# PCB_sch_iter2.net
KiCad netlist of a schematic drawn in EAGLE
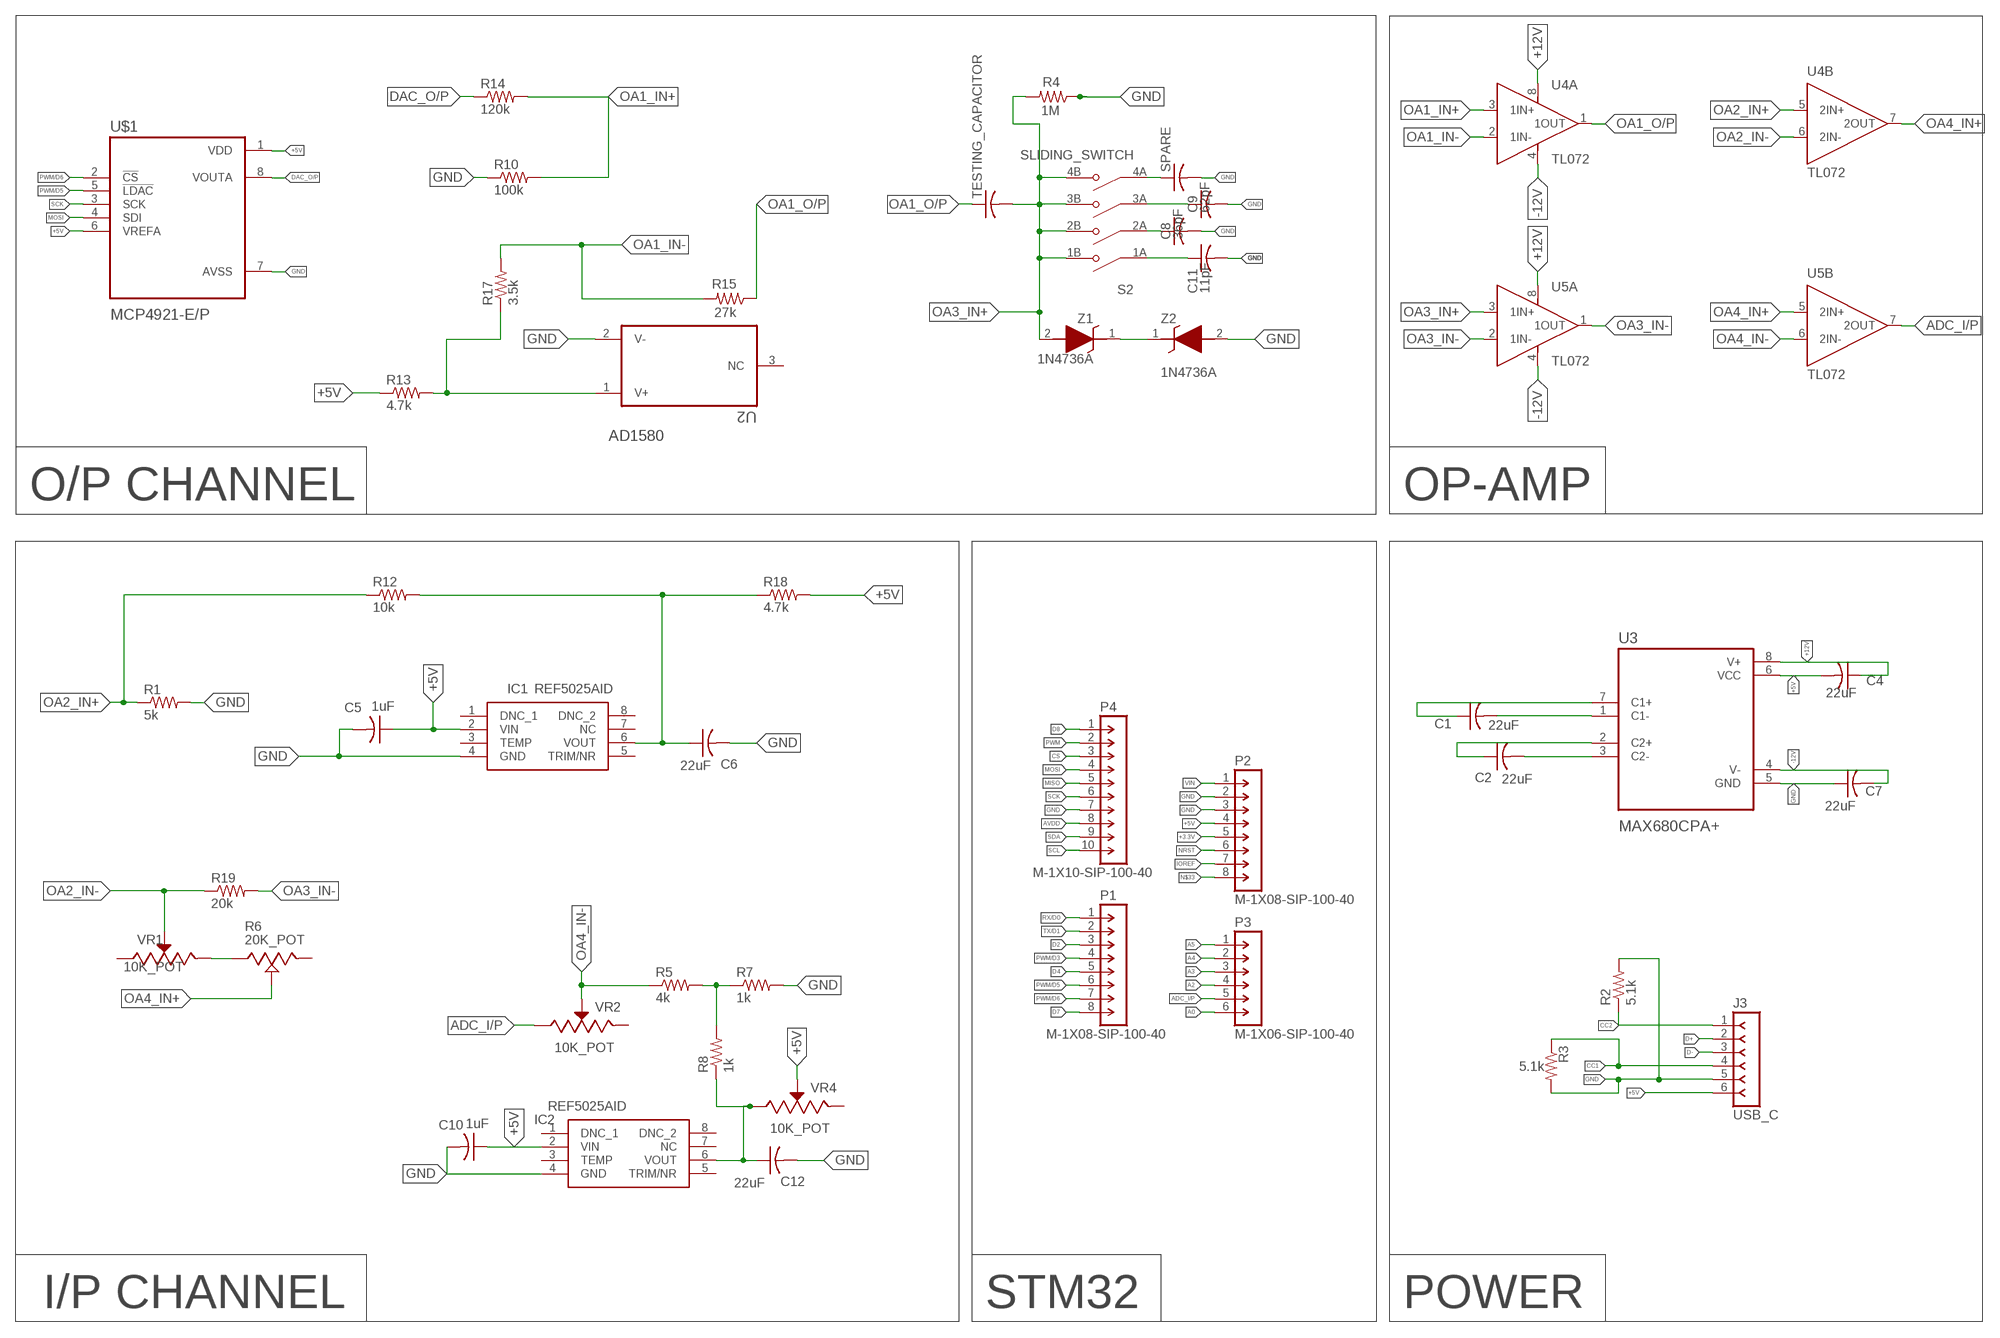
[diagram p0: schematic, sheet 1]

(export (version "E")
  (design (tool "Eeschema 10.0.6"))
  (components
    (comp (ref "C1")
      (value "22uF")
      (footprint "eagle-import:C1206")
      (libsource (lib "eagle-import") (part "C-USC1206"))
    )
    (comp (ref "C2")
      (value "22uF")
      (footprint "eagle-import:C1206")
      (libsource (lib "eagle-import") (part "C-USC1206"))
    )
    (comp (ref "C4")
      (value "22uF")
      (footprint "eagle-import:C1206")
      (libsource (lib "eagle-import") (part "C-USC1206"))
    )
    (comp (ref "C5")
      (value "1uF")
      (footprint "eagle-import:C1206")
      (libsource (lib "eagle-import") (part "C-USC1206"))
    )
    (comp (ref "C6")
      (value "22uF")
      (footprint "eagle-import:C1206")
      (libsource (lib "eagle-import") (part "C-USC1206"))
    )
    (comp (ref "C7")
      (value "22uF")
      (footprint "eagle-import:C1206")
      (libsource (lib "eagle-import") (part "C-USC1206"))
    )
    (comp (ref "C8")
      (value "36pF")
      (footprint "eagle-import:C0805")
      (libsource (lib "eagle-import") (part "C-USC0805"))
    )
    (comp (ref "C9")
      (value "62pF")
      (footprint "eagle-import:C0805")
      (libsource (lib "eagle-import") (part "C-USC0805"))
    )
    (comp (ref "C10")
      (value "1uF")
      (footprint "eagle-import:C1206")
      (libsource (lib "eagle-import") (part "C-USC1206"))
    )
    (comp (ref "C11")
      (value "11pF")
      (footprint "eagle-import:C0805")
      (fields (field (name "SPICEPREFIX") "C"))
      (libsource (lib "eagle-import") (part "C-USC0805"))
    )
    (comp (ref "C12")
      (value "22uF")
      (footprint "eagle-import:C1206")
      (libsource (lib "eagle-import") (part "C-USC1206"))
    )
    (comp (ref "IC1")
      (value "REF5025AID")
      (footprint "eagle-import:SOIC127P600X175-8N")
      (fields (field (name "MOUSER_PART_NUMBER") "595-REF5025AID"))
      (libsource (lib "eagle-import") (part "REF5025AID"))
    )
    (comp (ref "IC2")
      (value "REF5025AID")
      (footprint "eagle-import:SOIC127P600X175-8N")
      (fields (field (name "MOUSER_PART_NUMBER") "595-REF5025AID"))
      (libsource (lib "eagle-import") (part "REF5025AID"))
    )
    (comp (ref "J3")
      (value "USB_C")
      (footprint "eagle-import:SIP-100-06-40Y")
      (libsource (lib "eagle-import") (part "F-1X06-SIP-100-40Y"))
    )
    (comp (ref "P1")
      (value "M-1X08-SIP-100-40")
      (footprint "eagle-import:SIP-100-08-40")
      (libsource (lib "eagle-import") (part "M-1X08-SIP-100-40"))
    )
    (comp (ref "P2")
      (value "M-1X08-SIP-100-40")
      (footprint "eagle-import:SIP-100-08-40")
      (libsource (lib "eagle-import") (part "M-1X08-SIP-100-40"))
    )
    (comp (ref "P3")
      (value "M-1X06-SIP-100-40")
      (footprint "eagle-import:SIP-100-06-40")
      (libsource (lib "eagle-import") (part "M-1X06-SIP-100-40"))
    )
    (comp (ref "P4")
      (value "M-1X10-SIP-100-40")
      (footprint "eagle-import:SIP-100-10-40")
      (libsource (lib "eagle-import") (part "M-1X10-SIP-100-40"))
    )
    (comp (ref "R1")
      (value "5k")
      (footprint "eagle-import:M1206")
      (libsource (lib "eagle-import") (part "R-US_M1206"))
    )
    (comp (ref "R2")
      (value "5.1k")
      (footprint "eagle-import:R1206")
      (libsource (lib "eagle-import") (part "R-US_R1206"))
    )
    (comp (ref "R3")
      (value "5.1k")
      (footprint "eagle-import:R1206")
      (libsource (lib "eagle-import") (part "R-US_R1206"))
    )
    (comp (ref "R4")
      (value "1M")
      (footprint "eagle-import:M1206")
      (libsource (lib "eagle-import") (part "R-US_M1206"))
    )
    (comp (ref "R5")
      (value "4k")
      (footprint "eagle-import:M1206")
      (libsource (lib "eagle-import") (part "R-US_M1206"))
    )
    (comp (ref "R6")
      (value "20K_POT")
      (footprint "eagle-import:TRIM_3296X-1-203LF")
      (fields (field (name "MF") "Bourns") (field (name "MP") "3296X-1-203LF"))
      (libsource (lib "eagle-import") (part "3296X-1-203LF"))
    )
    (comp (ref "R7")
      (value "1k")
      (footprint "eagle-import:M1206")
      (libsource (lib "eagle-import") (part "R-US_M1206"))
    )
    (comp (ref "R8")
      (value "1k")
      (footprint "eagle-import:M1206")
      (libsource (lib "eagle-import") (part "R-US_M1206"))
    )
    (comp (ref "R10")
      (value "100k")
      (footprint "eagle-import:M1206")
      (libsource (lib "eagle-import") (part "R-US_M1206"))
    )
    (comp (ref "R12")
      (value "10k")
      (footprint "eagle-import:M1206")
      (libsource (lib "eagle-import") (part "R-US_M1206"))
    )
    (comp (ref "R13")
      (value "4.7k")
      (footprint "eagle-import:M1206")
      (libsource (lib "eagle-import") (part "R-US_M1206"))
    )
    (comp (ref "R14")
      (value "120k")
      (footprint "eagle-import:M1206")
      (libsource (lib "eagle-import") (part "R-US_M1206"))
    )
    (comp (ref "R15")
      (value "27k")
      (footprint "eagle-import:M1206")
      (libsource (lib "eagle-import") (part "R-US_M1206"))
    )
    (comp (ref "R17")
      (value "3.5k")
      (footprint "eagle-import:M1206")
      (libsource (lib "eagle-import") (part "R-US_M1206"))
    )
    (comp (ref "R18")
      (value "4.7k")
      (footprint "eagle-import:M1206")
      (libsource (lib "eagle-import") (part "R-US_M1206"))
    )
    (comp (ref "R19")
      (value "20k")
      (footprint "eagle-import:M1206")
      (libsource (lib "eagle-import") (part "R-US_M1206"))
    )
    (comp (ref "S2")
      (value "SLIDING_SWITCH")
      (footprint "eagle-import:SW_DS01C-254-S-04BE")
      (fields (field (name "MANUFACTURER") "CUI"))
      (libsource (lib "eagle-import") (part "DS01C-254-S-04BE"))
    )
    (comp (ref "SPARE")
      (value "C-USC0805")
      (footprint "eagle-import:C0805")
      (libsource (lib "eagle-import") (part "C-USC0805"))
    )
    (comp (ref "TESTING_CAPACITOR")
      (value "C-US050-030X075")
      (footprint "eagle-import:C050-030X075")
      (libsource (lib "eagle-import") (part "C-US050-030X075"))
    )
    (comp (ref "U$1")
      (value "MCP4921-E/P")
      (footprint "eagle-import:DIP787W46P254L927H533Q8")
      (fields (field (name "MF") "Microchip"))
      (libsource (lib "eagle-import") (part "MCP4921-E/P"))
    )
    (comp (ref "U2")
      (value "AD1580")
      (footprint "eagle-import:SOT96P237X112-3N")
      (libsource (lib "eagle-import") (part "AD1580BRTZ-R2-REEL7"))
    )
    (comp (ref "U3")
      (value "MAX680CPA+")
      (footprint "eagle-import:DIP794W47P254L991H457Q8")
      (fields (field (name "MF") "Maxim Integrated Products"))
      (libsource (lib "eagle-import") (part "MAX680CPA+"))
    )
    (comp (ref "U4")
      (value "TL072")
      (footprint "eagle-import:DIP794W45P254L1060H508Q8")
      (fields (field (name "MF") "Texas Instruments"))
      (libsource (lib "eagle-import") (part "TL072"))
    )
    (comp (ref "U5")
      (value "TL072")
      (footprint "eagle-import:DIP794W45P254L1060H508Q8")
      (fields (field (name "MF") "Texas Instruments"))
      (libsource (lib "eagle-import") (part "TL072"))
    )
    (comp (ref "VR1")
      (value "10K_POT")
      (footprint "eagle-import:TRIM_3296W-1-103RLF")
      (fields (field (name "MF") "Bourns") (field (name "MP") "3296W-1-103RLF"))
      (libsource (lib "eagle-import") (part "3296W-1-103RLF"))
    )
    (comp (ref "VR2")
      (value "10K_POT")
      (footprint "eagle-import:TRIM_3296W-1-103RLF")
      (fields (field (name "MF") "Bourns") (field (name "MP") "3296W-1-103RLF"))
      (libsource (lib "eagle-import") (part "3296W-1-103RLF"))
    )
    (comp (ref "VR4")
      (value "10K_POT")
      (footprint "eagle-import:TRIM_3296W-1-103RLF")
      (fields (field (name "MF") "Bourns") (field (name "MP") "3296W-1-103RLF"))
      (libsource (lib "eagle-import") (part "3296W-1-103RLF"))
    )
    (comp (ref "Z1")
      (value "1N4736A")
      (footprint "eagle-import:DIOAD1413W86L463D238")
      (fields (field (name "MOUSER_PART_NUMBER") "512-1N4736A"))
      (libsource (lib "eagle-import") (part "1N4736A"))
    )
    (comp (ref "Z2")
      (value "1N4736A")
      (footprint "eagle-import:DIOAD1413W86L463D238")
      (fields (field (name "MOUSER_PART_NUMBER") "512-1N4736A"))
      (libsource (lib "eagle-import") (part "1N4736A"))
    )
  )
  (nets
    (net (code "1") (name "+3.3V") (class "Default")
      (node (ref "P2") (pin "5") (pinfunction "5_5") (pintype "passive"))
    )
    (net (code "2") (name "+5V") (class "Default")
      (node (ref "C10") (pin "1") (pinfunction "1_1") (pintype "passive"))
      (node (ref "C4") (pin "2") (pinfunction "2_2") (pintype "passive"))
      (node (ref "C5") (pin "1") (pinfunction "1_1") (pintype "passive"))
      (node (ref "IC1") (pin "2") (pinfunction "VIN_2") (pintype "bidirectional"))
      (node (ref "IC2") (pin "2") (pinfunction "VIN_2") (pintype "bidirectional"))
      (node (ref "J3") (pin "6") (pinfunction "6_6") (pintype "passive"))
      (node (ref "P2") (pin "4") (pinfunction "4_4") (pintype "passive"))
      (node (ref "R13") (pin "1") (pinfunction "1_1") (pintype "passive"))
      (node (ref "R18") (pin "2") (pinfunction "2_2") (pintype "passive"))
      (node (ref "U$1") (pin "1") (pinfunction "VDD_1") (pintype "power_in"))
      (node (ref "U$1") (pin "6") (pinfunction "VREFA_6") (pintype "input"))
      (node (ref "U3") (pin "6") (pinfunction "VCC_6") (pintype "power_in"))
      (node (ref "VR4") (pin "2") (pinfunction "WIPER_2") (pintype "passive"))
    )
    (net (code "3") (name "+12V") (class "Default")
      (node (ref "C4") (pin "1") (pinfunction "1_1") (pintype "passive"))
      (node (ref "U3") (pin "8") (pinfunction "V+_8") (pintype "power_in"))
      (node (ref "U4") (pin "8") (pinfunction "VCC+_8") (pintype "power_in"))
      (node (ref "U5") (pin "8") (pinfunction "VCC+_8") (pintype "power_in"))
    )
    (net (code "4") (name "-12V") (class "Default")
      (node (ref "C7") (pin "2") (pinfunction "2_2") (pintype "passive"))
      (node (ref "U3") (pin "4") (pinfunction "V-_4") (pintype "power_in"))
      (node (ref "U4") (pin "4") (pinfunction "VCC-_4") (pintype "power_in"))
      (node (ref "U5") (pin "4") (pinfunction "VCC-_4") (pintype "power_in"))
    )
    (net (code "5") (name "A0") (class "Default")
      (node (ref "P3") (pin "6") (pinfunction "6_6") (pintype "passive"))
    )
    (net (code "6") (name "A2") (class "Default")
      (node (ref "P3") (pin "4") (pinfunction "4_4") (pintype "passive"))
    )
    (net (code "7") (name "A3") (class "Default")
      (node (ref "P3") (pin "3") (pinfunction "3_3") (pintype "passive"))
    )
    (net (code "8") (name "A4") (class "Default")
      (node (ref "P3") (pin "2") (pinfunction "2_2") (pintype "passive"))
    )
    (net (code "9") (name "A5") (class "Default")
      (node (ref "P3") (pin "1") (pinfunction "1_1") (pintype "passive"))
    )
    (net (code "10") (name "ADC_I{slash}P") (class "Default")
      (node (ref "P3") (pin "5") (pinfunction "5_5") (pintype "passive"))
      (node (ref "U5") (pin "7") (pinfunction "2OUT_7") (pintype "output"))
      (node (ref "VR2") (pin "1") (pinfunction "CCW_1") (pintype "passive"))
    )
    (net (code "11") (name "AVDD") (class "Default")
      (node (ref "P4") (pin "8") (pinfunction "8_8") (pintype "passive"))
    )
    (net (code "12") (name "CC1") (class "Default")
      (node (ref "J3") (pin "4") (pinfunction "4_4") (pintype "passive"))
      (node (ref "R3") (pin "1") (pinfunction "1_1") (pintype "passive"))
    )
    (net (code "13") (name "CC2") (class "Default")
      (node (ref "J3") (pin "1") (pinfunction "1_1") (pintype "passive"))
      (node (ref "R2") (pin "1") (pinfunction "1_1") (pintype "passive"))
    )
    (net (code "14") (name "CS") (class "Default")
      (node (ref "P4") (pin "3") (pinfunction "3_3") (pintype "passive"))
    )
    (net (code "15") (name "D+") (class "Default")
      (node (ref "J3") (pin "2") (pinfunction "2_2") (pintype "passive"))
    )
    (net (code "16") (name "D-") (class "Default")
      (node (ref "J3") (pin "3") (pinfunction "3_3") (pintype "passive"))
    )
    (net (code "17") (name "D2") (class "Default")
      (node (ref "P1") (pin "3") (pinfunction "3_3") (pintype "passive"))
    )
    (net (code "18") (name "D4") (class "Default")
      (node (ref "P1") (pin "5") (pinfunction "5_5") (pintype "passive"))
    )
    (net (code "19") (name "D7") (class "Default")
      (node (ref "P1") (pin "8") (pinfunction "8_8") (pintype "passive"))
    )
    (net (code "20") (name "D8") (class "Default")
      (node (ref "P4") (pin "1") (pinfunction "1_1") (pintype "passive"))
    )
    (net (code "21") (name "DAC_O{slash}P") (class "Default")
      (node (ref "R14") (pin "1") (pinfunction "1_1") (pintype "passive"))
      (node (ref "U$1") (pin "8") (pinfunction "VOUTA_8") (pintype "output"))
    )
    (net (code "22") (name "GND") (class "Default")
      (node (ref "C10") (pin "2") (pinfunction "2_2") (pintype "passive"))
      (node (ref "C11") (pin "2") (pinfunction "2_2") (pintype "passive"))
      (node (ref "C12") (pin "2") (pinfunction "2_2") (pintype "passive"))
      (node (ref "C5") (pin "2") (pinfunction "2_2") (pintype "passive"))
      (node (ref "C6") (pin "2") (pinfunction "2_2") (pintype "passive"))
      (node (ref "C7") (pin "1") (pinfunction "1_1") (pintype "passive"))
      (node (ref "C8") (pin "2") (pinfunction "2_2") (pintype "passive"))
      (node (ref "C9") (pin "2") (pinfunction "2_2") (pintype "passive"))
      (node (ref "IC1") (pin "4") (pinfunction "GND_4") (pintype "bidirectional"))
      (node (ref "IC2") (pin "4") (pinfunction "GND_4") (pintype "bidirectional"))
      (node (ref "J3") (pin "5") (pinfunction "5_5") (pintype "passive"))
      (node (ref "P2") (pin "2") (pinfunction "2_2") (pintype "passive"))
      (node (ref "P2") (pin "3") (pinfunction "3_3") (pintype "passive"))
      (node (ref "P4") (pin "7") (pinfunction "7_7") (pintype "passive"))
      (node (ref "R1") (pin "2") (pinfunction "2_2") (pintype "passive"))
      (node (ref "R10") (pin "1") (pinfunction "1_1") (pintype "passive"))
      (node (ref "R2") (pin "2") (pinfunction "2_2") (pintype "passive"))
      (node (ref "R3") (pin "2") (pinfunction "2_2") (pintype "passive"))
      (node (ref "R4") (pin "1") (pinfunction "1_1") (pintype "passive"))
      (node (ref "R7") (pin "2") (pinfunction "2_2") (pintype "passive"))
      (node (ref "SPARE") (pin "2") (pinfunction "2_2") (pintype "passive"))
      (node (ref "U$1") (pin "7") (pinfunction "AVSS_7") (pintype "power_in"))
      (node (ref "U2") (pin "2") (pinfunction "V-_2") (pintype "power_in"))
      (node (ref "U3") (pin "5") (pinfunction "GND_5") (pintype "power_in"))
      (node (ref "Z2") (pin "2") (pinfunction "A_2") (pintype "bidirectional"))
    )
    (net (code "23") (name "IOREF") (class "Default")
      (node (ref "P2") (pin "7") (pinfunction "7_7") (pintype "passive"))
    )
    (net (code "24") (name "MISO") (class "Default")
      (node (ref "P4") (pin "5") (pinfunction "5_5") (pintype "passive"))
    )
    (net (code "25") (name "MOSI") (class "Default")
      (node (ref "P4") (pin "4") (pinfunction "4_4") (pintype "passive"))
      (node (ref "U$1") (pin "4") (pinfunction "SDI_4") (pintype "input"))
    )
    (net (code "26") (name "N$33") (class "Default")
      (node (ref "P2") (pin "8") (pinfunction "8_8") (pintype "passive"))
    )
    (net (code "27") (name "NRST") (class "Default")
      (node (ref "P2") (pin "6") (pinfunction "6_6") (pintype "passive"))
    )
    (net (code "28") (name "Net-(IC1-VOUT)") (class "Default")
      (node (ref "C6") (pin "1") (pinfunction "1_1") (pintype "passive"))
      (node (ref "IC1") (pin "6") (pinfunction "VOUT_6") (pintype "bidirectional"))
      (node (ref "R12") (pin "2") (pinfunction "2_2") (pintype "passive"))
      (node (ref "R18") (pin "1") (pinfunction "1_1") (pintype "passive"))
    )
    (net (code "29") (name "Net-(IC2-VOUT)") (class "Default")
      (node (ref "C12") (pin "1") (pinfunction "1_1") (pintype "passive"))
      (node (ref "IC2") (pin "6") (pinfunction "VOUT_6") (pintype "bidirectional"))
      (node (ref "R8") (pin "1") (pinfunction "1_1") (pintype "passive"))
      (node (ref "VR4") (pin "1") (pinfunction "CCW_1") (pintype "passive"))
    )
    (net (code "30") (name "Net-(R5-Pad2)") (class "Default")
      (node (ref "R5") (pin "2") (pinfunction "2_2") (pintype "passive"))
      (node (ref "R7") (pin "1") (pinfunction "1_1") (pintype "passive"))
      (node (ref "R8") (pin "2") (pinfunction "2_2") (pintype "passive"))
    )
    (net (code "31") (name "Net-(R6-CCW)") (class "Default")
      (node (ref "R6") (pin "1") (pinfunction "CCW_1") (pintype "passive"))
      (node (ref "VR1") (pin "3") (pinfunction "CW_3") (pintype "passive"))
    )
    (net (code "32") (name "Net-(S2-COM1)") (class "Default")
      (node (ref "C11") (pin "1") (pinfunction "1_1") (pintype "passive"))
      (node (ref "S2") (pin "1A") (pinfunction "COM1_1A") (pintype "passive"))
    )
    (net (code "33") (name "Net-(S2-COM2)") (class "Default")
      (node (ref "C8") (pin "1") (pinfunction "1_1") (pintype "passive"))
      (node (ref "S2") (pin "2A") (pinfunction "COM2_2A") (pintype "passive"))
    )
    (net (code "34") (name "Net-(S2-COM3)") (class "Default")
      (node (ref "C9") (pin "1") (pinfunction "1_1") (pintype "passive"))
      (node (ref "S2") (pin "3A") (pinfunction "COM3_3A") (pintype "passive"))
    )
    (net (code "35") (name "Net-(S2-COM4)") (class "Default")
      (node (ref "S2") (pin "4A") (pinfunction "COM4_4A") (pintype "passive"))
      (node (ref "SPARE") (pin "1") (pinfunction "1_1") (pintype "passive"))
    )
    (net (code "36") (name "Net-(U2-V+)") (class "Default")
      (node (ref "R13") (pin "2") (pinfunction "2_2") (pintype "passive"))
      (node (ref "R17") (pin "1") (pinfunction "1_1") (pintype "passive"))
      (node (ref "U2") (pin "1") (pinfunction "V+_1") (pintype "power_in"))
    )
    (net (code "37") (name "Net-(U3-C1+)") (class "Default")
      (node (ref "C1") (pin "1") (pinfunction "1_1") (pintype "passive"))
      (node (ref "U3") (pin "7") (pinfunction "C1+_7") (pintype "passive"))
    )
    (net (code "38") (name "Net-(U3-C1-)") (class "Default")
      (node (ref "C1") (pin "2") (pinfunction "2_2") (pintype "passive"))
      (node (ref "U3") (pin "1") (pinfunction "C1-_1") (pintype "passive"))
    )
    (net (code "39") (name "Net-(U3-C2+)") (class "Default")
      (node (ref "C2") (pin "1") (pinfunction "1_1") (pintype "passive"))
      (node (ref "U3") (pin "2") (pinfunction "C2+_2") (pintype "passive"))
    )
    (net (code "40") (name "Net-(U3-C2-)") (class "Default")
      (node (ref "C2") (pin "2") (pinfunction "2_2") (pintype "passive"))
      (node (ref "U3") (pin "3") (pinfunction "C2-_3") (pintype "passive"))
    )
    (net (code "41") (name "Net-(Z1-K)") (class "Default")
      (node (ref "Z1") (pin "1") (pinfunction "K_1") (pintype "bidirectional"))
      (node (ref "Z2") (pin "1") (pinfunction "K_1") (pintype "bidirectional"))
    )
    (net (code "42") (name "OA1_IN+") (class "Default")
      (node (ref "R10") (pin "2") (pinfunction "2_2") (pintype "passive"))
      (node (ref "R14") (pin "2") (pinfunction "2_2") (pintype "passive"))
      (node (ref "U4") (pin "3") (pinfunction "1IN+_3") (pintype "input"))
    )
    (net (code "43") (name "OA1_IN-") (class "Default")
      (node (ref "R15") (pin "2") (pinfunction "2_2") (pintype "passive"))
      (node (ref "R17") (pin "2") (pinfunction "2_2") (pintype "passive"))
      (node (ref "U4") (pin "2") (pinfunction "1IN-_2") (pintype "input"))
    )
    (net (code "44") (name "OA1_O{slash}P") (class "Default")
      (node (ref "R15") (pin "1") (pinfunction "1_1") (pintype "passive"))
      (node (ref "TESTING_CAPACITOR") (pin "1") (pinfunction "1_1") (pintype "passive"))
      (node (ref "U4") (pin "1") (pinfunction "1OUT_1") (pintype "output"))
    )
    (net (code "45") (name "OA2_IN+") (class "Default")
      (node (ref "R1") (pin "1") (pinfunction "1_1") (pintype "passive"))
      (node (ref "R12") (pin "1") (pinfunction "1_1") (pintype "passive"))
      (node (ref "U4") (pin "5") (pinfunction "2IN+_5") (pintype "input"))
    )
    (net (code "46") (name "OA2_IN-") (class "Default")
      (node (ref "R19") (pin "1") (pinfunction "1_1") (pintype "passive"))
      (node (ref "U4") (pin "6") (pinfunction "2IN-_6") (pintype "input"))
      (node (ref "VR1") (pin "2") (pinfunction "WIPER_2") (pintype "passive"))
    )
    (net (code "47") (name "OA3_IN+") (class "Default")
      (node (ref "R4") (pin "2") (pinfunction "2_2") (pintype "passive"))
      (node (ref "S2") (pin "1B") (pinfunction "NO1_1B") (pintype "passive"))
      (node (ref "S2") (pin "2B") (pinfunction "NO2_2B") (pintype "passive"))
      (node (ref "S2") (pin "3B") (pinfunction "NO3_3B") (pintype "passive"))
      (node (ref "S2") (pin "4B") (pinfunction "NO4_4B") (pintype "passive"))
      (node (ref "TESTING_CAPACITOR") (pin "2") (pinfunction "2_2") (pintype "passive"))
      (node (ref "U5") (pin "3") (pinfunction "1IN+_3") (pintype "input"))
      (node (ref "Z1") (pin "2") (pinfunction "A_2") (pintype "bidirectional"))
    )
    (net (code "48") (name "OA3_IN-") (class "Default")
      (node (ref "R19") (pin "2") (pinfunction "2_2") (pintype "passive"))
      (node (ref "U5") (pin "1") (pinfunction "1OUT_1") (pintype "output"))
      (node (ref "U5") (pin "2") (pinfunction "1IN-_2") (pintype "input"))
    )
    (net (code "49") (name "OA4_IN+") (class "Default")
      (node (ref "R6") (pin "2") (pinfunction "WIPER_2") (pintype "passive"))
      (node (ref "U4") (pin "7") (pinfunction "2OUT_7") (pintype "output"))
      (node (ref "U5") (pin "5") (pinfunction "2IN+_5") (pintype "input"))
    )
    (net (code "50") (name "OA4_IN-") (class "Default")
      (node (ref "R5") (pin "1") (pinfunction "1_1") (pintype "passive"))
      (node (ref "U5") (pin "6") (pinfunction "2IN-_6") (pintype "input"))
      (node (ref "VR2") (pin "2") (pinfunction "WIPER_2") (pintype "passive"))
    )
    (net (code "51") (name "PWM") (class "Default")
      (node (ref "P4") (pin "2") (pinfunction "2_2") (pintype "passive"))
    )
    (net (code "52") (name "PWM{slash}D3") (class "Default")
      (node (ref "P1") (pin "4") (pinfunction "4_4") (pintype "passive"))
    )
    (net (code "53") (name "PWM{slash}D5") (class "Default")
      (node (ref "P1") (pin "6") (pinfunction "6_6") (pintype "passive"))
      (node (ref "U$1") (pin "5") (pinfunction "~{LDAC}_5") (pintype "input"))
    )
    (net (code "54") (name "PWM{slash}D6") (class "Default")
      (node (ref "P1") (pin "7") (pinfunction "7_7") (pintype "passive"))
      (node (ref "U$1") (pin "2") (pinfunction "~{CS}_2") (pintype "input"))
    )
    (net (code "55") (name "RX{slash}D0") (class "Default")
      (node (ref "P1") (pin "1") (pinfunction "1_1") (pintype "passive"))
    )
    (net (code "56") (name "SCK") (class "Default")
      (node (ref "P4") (pin "6") (pinfunction "6_6") (pintype "passive"))
      (node (ref "U$1") (pin "3") (pinfunction "SCK_3") (pintype "input"))
    )
    (net (code "57") (name "SCL") (class "Default")
      (node (ref "P4") (pin "10") (pinfunction "10_10") (pintype "passive"))
    )
    (net (code "58") (name "SDA") (class "Default")
      (node (ref "P4") (pin "9") (pinfunction "9_9") (pintype "passive"))
    )
    (net (code "59") (name "TX{slash}D1") (class "Default")
      (node (ref "P1") (pin "2") (pinfunction "2_2") (pintype "passive"))
    )
    (net (code "60") (name "VIN") (class "Default")
      (node (ref "P2") (pin "1") (pinfunction "1_1") (pintype "passive"))
    )
    (net (code "61") (name "unconnected-(IC1-DNC_1-Pad1)") (class "Default")
      (node (ref "IC1") (pin "1") (pinfunction "DNC_1_1") (pintype "bidirectional"))
    )
    (net (code "62") (name "unconnected-(IC1-DNC_2-Pad8)") (class "Default")
      (node (ref "IC1") (pin "8") (pinfunction "DNC_2_8") (pintype "bidirectional"))
    )
    (net (code "63") (name "unconnected-(IC1-NC-Pad7)") (class "Default")
      (node (ref "IC1") (pin "7") (pinfunction "NC_7") (pintype "no_connect"))
    )
    (net (code "64") (name "unconnected-(IC1-TEMP-Pad3)") (class "Default")
      (node (ref "IC1") (pin "3") (pinfunction "TEMP_3") (pintype "bidirectional"))
    )
    (net (code "65") (name "unconnected-(IC1-TRIM{slash}NR-Pad5)") (class "Default")
      (node (ref "IC1") (pin "5") (pinfunction "TRIM/NR_5") (pintype "bidirectional"))
    )
    (net (code "66") (name "unconnected-(IC2-DNC_1-Pad1)") (class "Default")
      (node (ref "IC2") (pin "1") (pinfunction "DNC_1_1") (pintype "bidirectional"))
    )
    (net (code "67") (name "unconnected-(IC2-DNC_2-Pad8)") (class "Default")
      (node (ref "IC2") (pin "8") (pinfunction "DNC_2_8") (pintype "bidirectional"))
    )
    (net (code "68") (name "unconnected-(IC2-NC-Pad7)") (class "Default")
      (node (ref "IC2") (pin "7") (pinfunction "NC_7") (pintype "no_connect"))
    )
    (net (code "69") (name "unconnected-(IC2-TEMP-Pad3)") (class "Default")
      (node (ref "IC2") (pin "3") (pinfunction "TEMP_3") (pintype "bidirectional"))
    )
    (net (code "70") (name "unconnected-(IC2-TRIM{slash}NR-Pad5)") (class "Default")
      (node (ref "IC2") (pin "5") (pinfunction "TRIM/NR_5") (pintype "bidirectional"))
    )
    (net (code "71") (name "unconnected-(R6-CW-Pad3)") (class "Default")
      (node (ref "R6") (pin "3") (pinfunction "CW_3") (pintype "passive"))
    )
    (net (code "72") (name "unconnected-(U2-NC-Pad3)") (class "Default")
      (node (ref "U2") (pin "3") (pinfunction "NC_3") (pintype "bidirectional"))
    )
    (net (code "73") (name "unconnected-(VR1-CCW-Pad1)") (class "Default")
      (node (ref "VR1") (pin "1") (pinfunction "CCW_1") (pintype "passive"))
    )
    (net (code "74") (name "unconnected-(VR2-CW-Pad3)") (class "Default")
      (node (ref "VR2") (pin "3") (pinfunction "CW_3") (pintype "passive"))
    )
    (net (code "75") (name "unconnected-(VR4-CW-Pad3)") (class "Default")
      (node (ref "VR4") (pin "3") (pinfunction "CW_3") (pintype "passive"))
    )
  )
)
